# untitled.net
KiCad netlist of a schematic drawn in EAGLE
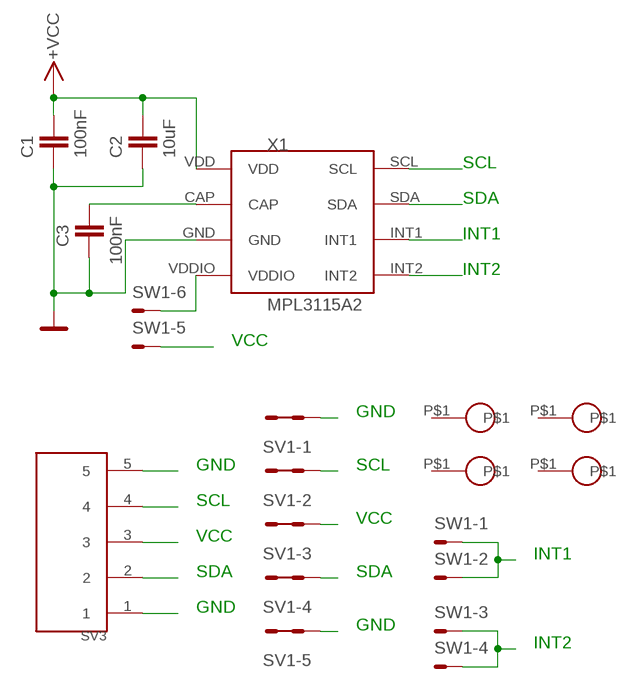
[diagram p0: schematic, sheet 1]

(export (version "E")
  (design (tool "Eeschema 10.0.6"))
  (components
    (comp (ref "C1")
      (value "100nF")
      (footprint "eagle-import:C0805")
      (libsource (lib "eagle-import") (part "C-EUC0805"))
    )
    (comp (ref "C2")
      (value "10uF")
      (footprint "eagle-import:C0805")
      (libsource (lib "eagle-import") (part "C-EUC0805"))
    )
    (comp (ref "C3")
      (value "100nF")
      (footprint "eagle-import:C0805")
      (libsource (lib "eagle-import") (part "C-EUC0805"))
    )
    (comp (ref "SV1")
      (value "MA05-2")
      (footprint "eagle-import:MA05-2")
      (libsource (lib "eagle-import") (part "MA05-2"))
    )
    (comp (ref "SV3")
      (value "SMD_MA05-01")
      (footprint "eagle-import:SMD_MA05-1")
      (libsource (lib "eagle-import") (part "SMD_MA05-01"))
    )
    (comp (ref "SW1")
      (value "MA03-3")
      (footprint "eagle-import:MA03-2")
      (libsource (lib "eagle-import") (part "MA03-3"))
    )
    (comp (ref "X1")
      (value "MPL3115A2")
      (footprint "eagle-import:LGA")
      (libsource (lib "eagle-import") (part "MPL3115A2"))
    )
    (comp (ref "X2")
      (value "SROUB3M")
      (footprint "eagle-import:SROUB3M")
      (libsource (lib "eagle-import") (part "SROUB3M"))
    )
    (comp (ref "X3")
      (value "SROUB3M")
      (footprint "eagle-import:SROUB3M")
      (libsource (lib "eagle-import") (part "SROUB3M"))
    )
    (comp (ref "X4")
      (value "SROUB3M")
      (footprint "eagle-import:SROUB3M")
      (libsource (lib "eagle-import") (part "SROUB3M"))
    )
    (comp (ref "X5")
      (value "SROUB3M")
      (footprint "eagle-import:SROUB3M")
      (libsource (lib "eagle-import") (part "SROUB3M"))
    )
  )
  (nets
    (net (code "1") (name "+VCC") (class "Default")
      (node (ref "C1") (pin "1") (pinfunction "1_1") (pintype "passive"))
      (node (ref "C2") (pin "1") (pinfunction "1_1") (pintype "passive"))
      (node (ref "SV1") (pin "5") (pinfunction "K_5") (pintype "passive"))
      (node (ref "SV1") (pin "6") (pinfunction "K_6") (pintype "passive"))
      (node (ref "SV3") (pin "3") (pinfunction "3_3") (pintype "bidirectional"))
      (node (ref "SW1") (pin "5") (pinfunction "P$1_5") (pintype "passive"))
      (node (ref "X1") (pin "VDD") (pinfunction "VDD_VDD") (pintype "bidirectional"))
    )
    (net (code "2") (name "/INT1") (class "Default")
      (node (ref "SW1") (pin "1") (pinfunction "P$1_1") (pintype "passive"))
      (node (ref "SW1") (pin "2") (pinfunction "P$1_2") (pintype "passive"))
      (node (ref "X1") (pin "INT1") (pinfunction "INT1_INT1") (pintype "bidirectional"))
    )
    (net (code "3") (name "/INT2") (class "Default")
      (node (ref "SW1") (pin "3") (pinfunction "P$1_3") (pintype "passive"))
      (node (ref "SW1") (pin "4") (pinfunction "P$1_4") (pintype "passive"))
      (node (ref "X1") (pin "INT2") (pinfunction "INT2_INT2") (pintype "bidirectional"))
    )
    (net (code "4") (name "/SCL") (class "Default")
      (node (ref "SV1") (pin "3") (pinfunction "K_3") (pintype "passive"))
      (node (ref "SV1") (pin "4") (pinfunction "K_4") (pintype "passive"))
      (node (ref "SV3") (pin "4") (pinfunction "4_4") (pintype "bidirectional"))
      (node (ref "X1") (pin "SCL") (pinfunction "SCL_SCL") (pintype "bidirectional"))
    )
    (net (code "5") (name "/SDA") (class "Default")
      (node (ref "SV1") (pin "7") (pinfunction "K_7") (pintype "passive"))
      (node (ref "SV1") (pin "8") (pinfunction "K_8") (pintype "passive"))
      (node (ref "SV3") (pin "2") (pinfunction "2_2") (pintype "bidirectional"))
      (node (ref "X1") (pin "SDA") (pinfunction "SDA_SDA") (pintype "bidirectional"))
    )
    (net (code "6") (name "GND") (class "Default")
      (node (ref "C1") (pin "2") (pinfunction "2_2") (pintype "passive"))
      (node (ref "C2") (pin "2") (pinfunction "2_2") (pintype "passive"))
      (node (ref "C3") (pin "2") (pinfunction "2_2") (pintype "passive"))
      (node (ref "SV1") (pin "1") (pinfunction "K_1") (pintype "passive"))
      (node (ref "SV1") (pin "10") (pinfunction "K_10") (pintype "passive"))
      (node (ref "SV1") (pin "2") (pinfunction "K_2") (pintype "passive"))
      (node (ref "SV1") (pin "9") (pinfunction "K_9") (pintype "passive"))
      (node (ref "SV3") (pin "1") (pinfunction "1_1") (pintype "bidirectional"))
      (node (ref "SV3") (pin "5") (pinfunction "5_5") (pintype "bidirectional"))
      (node (ref "X1") (pin "GND") (pinfunction "GND_GND") (pintype "bidirectional"))
    )
    (net (code "7") (name "Net-(C3-Pad1)") (class "Default")
      (node (ref "C3") (pin "1") (pinfunction "1_1") (pintype "passive"))
      (node (ref "X1") (pin "CAP") (pinfunction "CAP_CAP") (pintype "bidirectional"))
    )
    (net (code "8") (name "Net-(SW1F-P$1)") (class "Default")
      (node (ref "SW1") (pin "6") (pinfunction "P$1_6") (pintype "passive"))
      (node (ref "X1") (pin "VDDIO") (pinfunction "VDDIO_VDDIO") (pintype "bidirectional"))
    )
    (net (code "9") (name "unconnected-(X2-PadP$1)") (class "Default")
      (node (ref "X2") (pin "P$1") (pinfunction "P$1_P$1") (pintype "passive"))
    )
    (net (code "10") (name "unconnected-(X3-PadP$1)") (class "Default")
      (node (ref "X3") (pin "P$1") (pinfunction "P$1_P$1") (pintype "passive"))
    )
    (net (code "11") (name "unconnected-(X4-PadP$1)") (class "Default")
      (node (ref "X4") (pin "P$1") (pinfunction "P$1_P$1") (pintype "passive"))
    )
    (net (code "12") (name "unconnected-(X5-PadP$1)") (class "Default")
      (node (ref "X5") (pin "P$1") (pinfunction "P$1_P$1") (pintype "passive"))
    )
  )
)
